# Microcontroller.net
KiCad netlist of a schematic drawn in Altium Designer
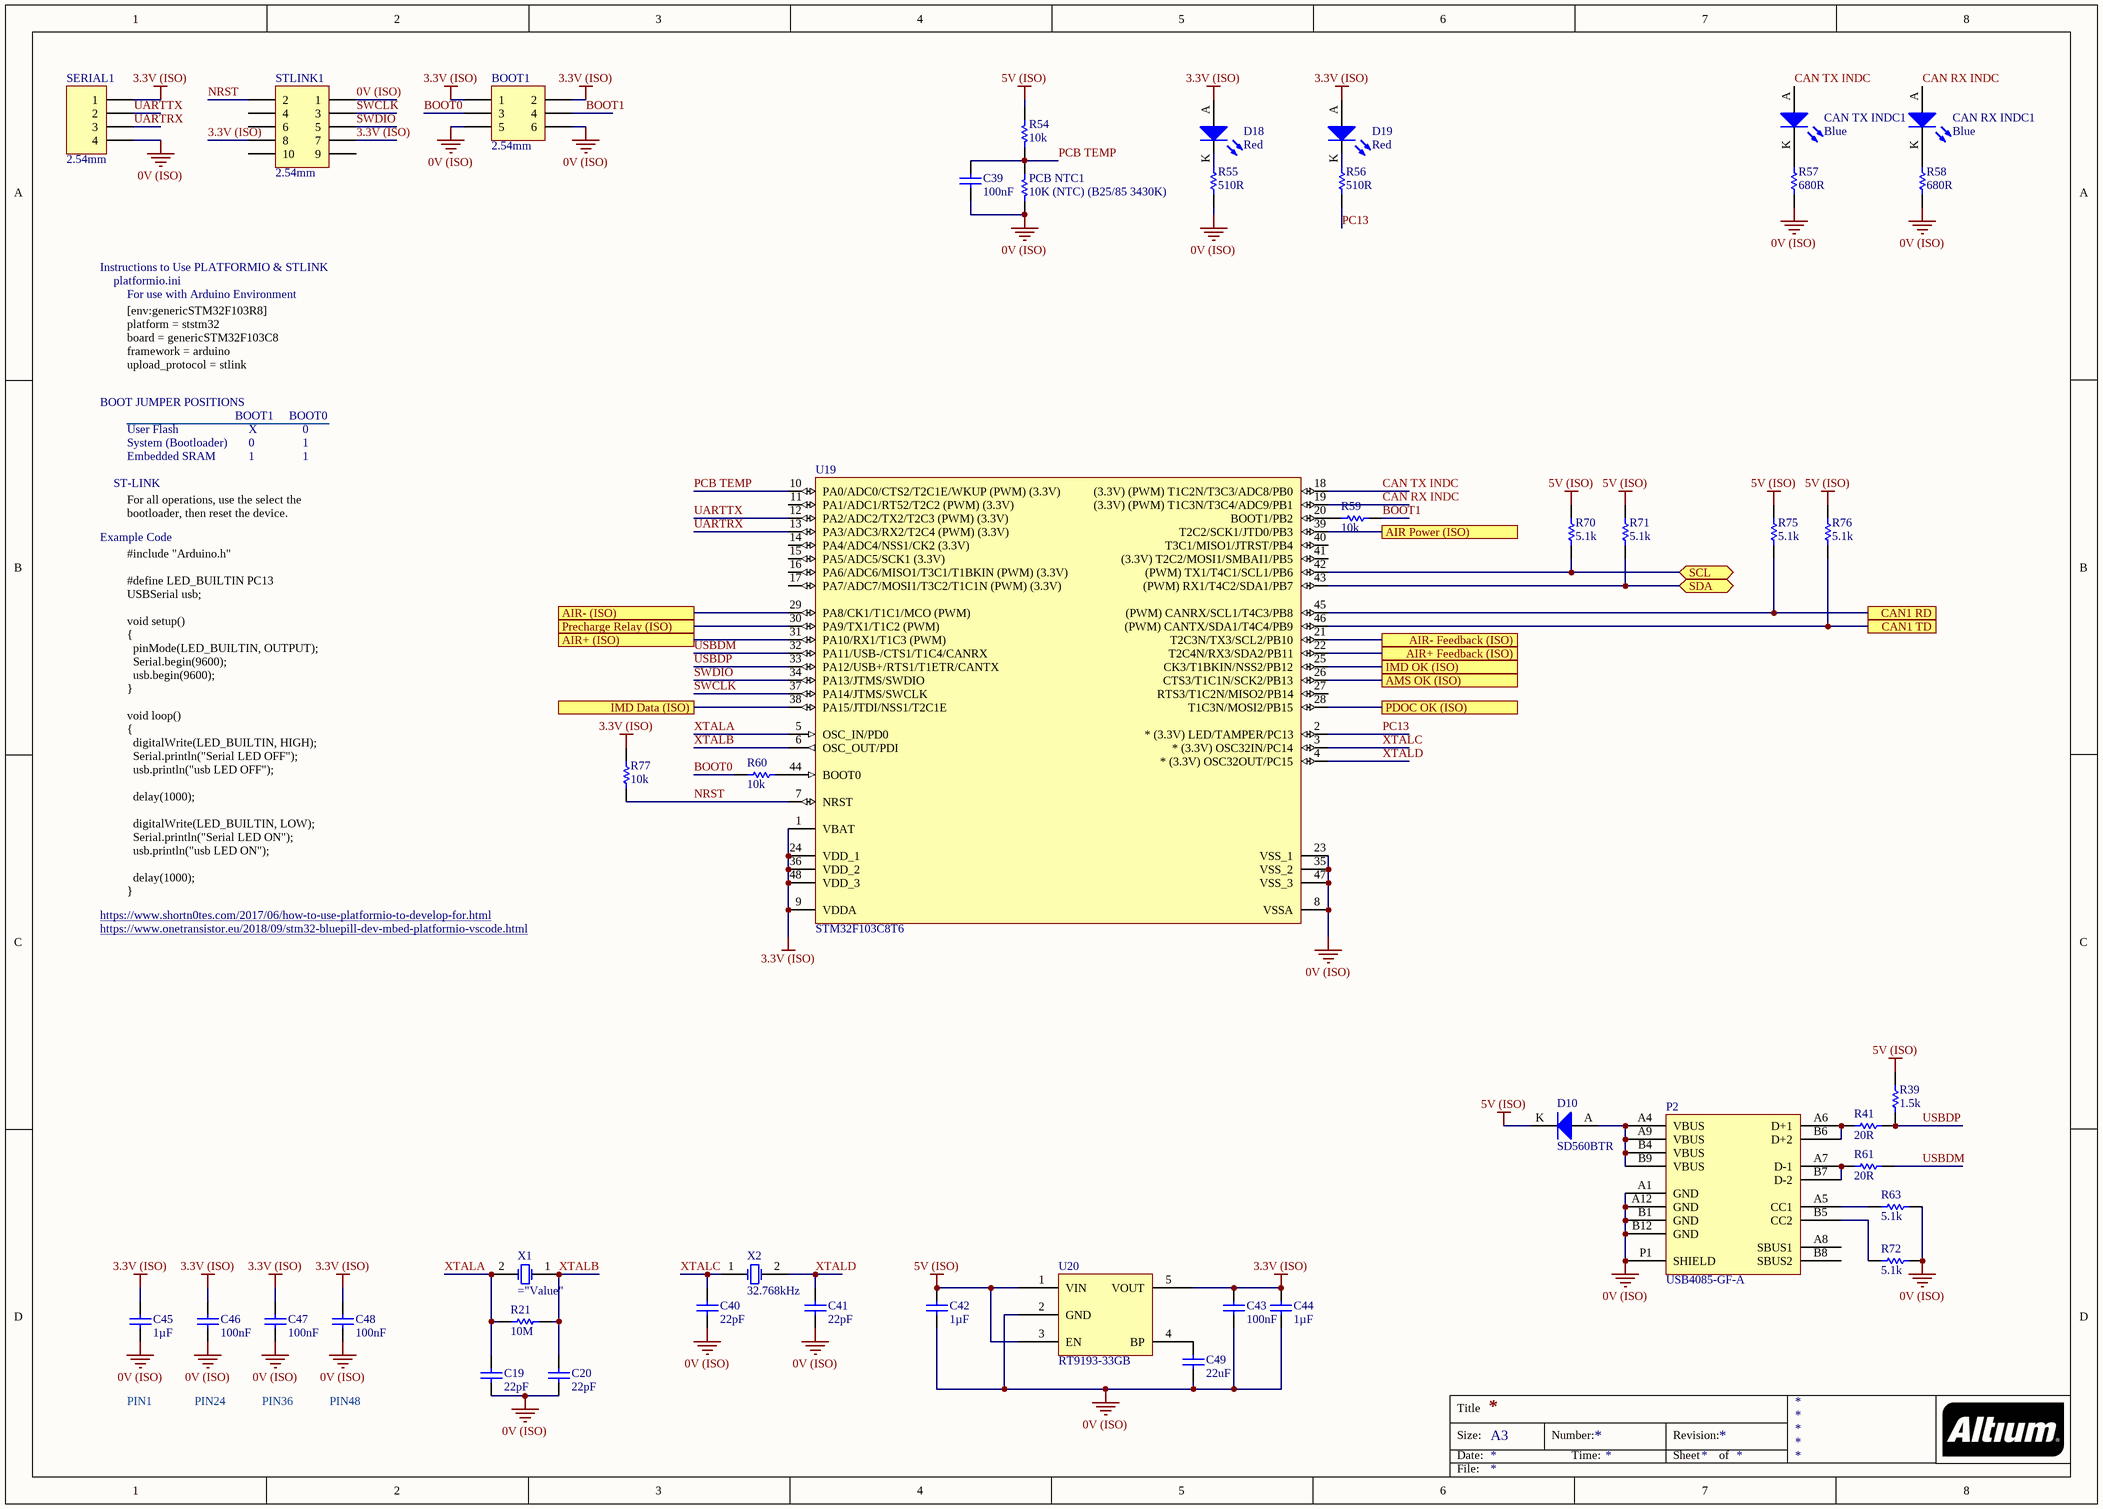
[diagram p0: Microcontroller.SchDoc]

(export (version "E")
  (design (tool "Eeschema 10.0.6"))
  (components
    (comp (ref "BOOT1")
      (value "2.54mm")
      (footprint "TH 2.54mm Header 2x3")
      (fields (field (name "PART NUMBER") "TH 2.54mm Header 2x3") (field (name "CONTACT") "NA"))
      (libsource (lib "ts_20-standard-connectors") (part "Header 2x3"))
    )
    (comp (ref "C19")
      (value "22pF")
      (footprint "0805")
      (fields
        (field (name "PART NUMBER") "GRM21A5C2E220JW01D")
        (field (name "TOLERANCE") "±5%")
        (field (name "MANUFACTURER") "muRata")
      )
      (libsource (lib "ts_20-standard-library") (part "Capacitor"))
    )
    (comp (ref "C20")
      (value "22pF")
      (footprint "0805")
      (fields
        (field (name "PART NUMBER") "GRM21A5C2E220JW01D")
        (field (name "TOLERANCE") "±5%")
        (field (name "MANUFACTURER") "muRata")
      )
      (libsource (lib "ts_20-standard-library") (part "Capacitor"))
    )
    (comp (ref "C39")
      (value "100nF")
      (footprint "0805")
      (fields
        (field (name "PART NUMBER") "GCM21BR71E104KA37L")
        (field (name "TOLERANCE") "10%")
        (field (name "MANUFACTURER") "muRata")
      )
      (libsource (lib "ts_20-standard-library") (part "Capacitor"))
    )
    (comp (ref "C40")
      (value "22pF")
      (footprint "0805")
      (fields
        (field (name "PART NUMBER") "GRM21A5C2E220JW01D")
        (field (name "TOLERANCE") "±5%")
        (field (name "MANUFACTURER") "muRata")
      )
      (libsource (lib "ts_20-standard-library") (part "Capacitor"))
    )
    (comp (ref "C41")
      (value "22pF")
      (footprint "0805")
      (fields
        (field (name "PART NUMBER") "GRM21A5C2E220JW01D")
        (field (name "TOLERANCE") "±5%")
        (field (name "MANUFACTURER") "muRata")
      )
      (libsource (lib "ts_20-standard-library") (part "Capacitor"))
    )
    (comp (ref "C42")
      (value "1µF")
      (footprint "0805")
      (fields
        (field (name "PART NUMBER") "GCM21BR71H105KA03L")
        (field (name "TOLERANCE") "±10%")
        (field (name "MANUFACTURER") "muRata")
      )
      (libsource (lib "ts_20-standard-library") (part "Capacitor"))
    )
    (comp (ref "C43")
      (value "100nF")
      (footprint "0805")
      (fields
        (field (name "PART NUMBER") "GCM21BR71H104KA37L")
        (field (name "TOLERANCE") "±10%")
        (field (name "MANUFACTURER") "muRata")
      )
      (libsource (lib "ts_20-standard-library") (part "Capacitor"))
    )
    (comp (ref "C44")
      (value "1µF")
      (footprint "0805")
      (fields
        (field (name "PART NUMBER") "GCM21BR71H105KA03L")
        (field (name "TOLERANCE") "±10%")
        (field (name "MANUFACTURER") "muRata")
      )
      (libsource (lib "ts_20-standard-library") (part "Capacitor"))
    )
    (comp (ref "C45")
      (value "1µF")
      (footprint "0805")
      (fields
        (field (name "PART NUMBER") "GCM21BR71H105KA03L")
        (field (name "TOLERANCE") "±10%")
        (field (name "MANUFACTURER") "muRata")
      )
      (libsource (lib "ts_20-standard-library") (part "Capacitor"))
    )
    (comp (ref "C46")
      (value "100nF")
      (footprint "0805")
      (fields
        (field (name "PART NUMBER") "GCM21BR71H104KA37L")
        (field (name "TOLERANCE") "±10%")
        (field (name "MANUFACTURER") "muRata")
      )
      (libsource (lib "ts_20-standard-library") (part "Capacitor"))
    )
    (comp (ref "C47")
      (value "100nF")
      (footprint "0805")
      (fields
        (field (name "PART NUMBER") "GCM21BR71H104KA37L")
        (field (name "TOLERANCE") "±10%")
        (field (name "MANUFACTURER") "muRata")
      )
      (libsource (lib "ts_20-standard-library") (part "Capacitor"))
    )
    (comp (ref "C48")
      (value "100nF")
      (footprint "0805")
      (fields
        (field (name "PART NUMBER") "GCM21BR71H104KA37L")
        (field (name "TOLERANCE") "±10%")
        (field (name "MANUFACTURER") "muRata")
      )
      (libsource (lib "ts_20-standard-library") (part "Capacitor"))
    )
    (comp (ref "C49")
      (value "22uF")
      (footprint "0805")
      (fields
        (field (name "PART NUMBER") "GRM21BR61A226ME51L")
        (field (name "TOLERANCE") "20%")
        (field (name "MANUFACTURER") "muRata")
      )
      (libsource (lib "ts_20-standard-library") (part "Capacitor"))
    )
    (comp (ref "CAN RX INDC1")
      (value "Blue")
      (footprint "0805 LED")
      (description "LED BLUE CLEAR 2012 SMD")
      (fields
        (field (name "PART NUMBER") "SML-MN2BCTT86C")
        (field (name "MANUFACTURER") "ROHM Semiconductor")
      )
      (libsource (lib "ts_20-standard-library") (part "LED"))
    )
    (comp (ref "CAN TX INDC1")
      (value "Blue")
      (footprint "0805 LED")
      (description "LED BLUE CLEAR 2012 SMD")
      (fields
        (field (name "PART NUMBER") "SML-MN2BCTT86C")
        (field (name "MANUFACTURER") "ROHM Semiconductor")
      )
      (libsource (lib "ts_20-standard-library") (part "LED"))
    )
    (comp (ref "D10")
      (value "SD560BTR")
      (footprint "SMB Diode")
      (description "1.2V_F 600V 5A SMB")
      (fields
        (field (name "MANUFACTURER") "SMC Diode Solutions")
        (field (name "DIGIKEY PART NUMBER") "1655-1530-2-ND")
      )
      (libsource (lib "ts_20-standard-library") (part "Diode"))
    )
    (comp (ref "D18")
      (value "Red")
      (footprint "0805 LED")
      (description "Red LED Indication - Discrete 1.75V 0805 (2012 Metric)")
      (fields (field (name "MANUFACTURER") "ROHM Semiconductor") (field (name "PART NUMBER") "SML-210LTT86"))
      (libsource (lib "ts_20-standard-library") (part "LED"))
    )
    (comp (ref "D19")
      (value "Red")
      (footprint "0805 LED")
      (description "Red LED Indication - Discrete 1.75V 0805 (2012 Metric)")
      (fields (field (name "MANUFACTURER") "ROHM Semiconductor") (field (name "PART NUMBER") "SML-210LTT86"))
      (libsource (lib "ts_20-standard-library") (part "LED"))
    )
    (comp (ref "P2")
      (value "USB4085-GF-A")
      (footprint "USB4085-GF-A")
      (description "USB - C (Type - C) USB 2.0 Receptacle Connector 16 Position Through Hole, Right Angle")
      (fields (field (name "DIGIKEY PART NUMBER") "2073-USB4085-GF-ACT-ND"))
      (libsource (lib "ts_20-standard-connectors") (part "USB4085-GF-A"))
    )
    (comp (ref "PCB NTC1")
      (value "10K (NTC) (B25/85 3430K)")
      (footprint "0805")
      (fields
        (field (name "PART NUMBER") "NTCS0805E3103FLT")
        (field (name "MANUFACTURER") "Vishay Beyschlag")
        (field (name "TOLERANCE") "0.01")
      )
      (libsource (lib "ts_20-standard-library") (part "Resistor"))
    )
    (comp (ref "R21")
      (value "10M")
      (footprint "0805")
      (fields
        (field (name "PART NUMBER") "RC0805FR0710ML")
        (field (name "MANUFACTURER") "YAGEO")
        (field (name "TOLERANCE") "0.01")
      )
      (libsource (lib "ts_20-standard-library") (part "Resistor"))
    )
    (comp (ref "R39")
      (value "1.5k")
      (footprint "0805")
      (fields
        (field (name "PART NUMBER") "RC0805FR071K5L")
        (field (name "MANUFACTURER") "YAGEO")
        (field (name "TOLERANCE") "0.01")
      )
      (libsource (lib "ts_20-standard-library") (part "Resistor"))
    )
    (comp (ref "R41")
      (value "20R")
      (footprint "0805")
      (fields
        (field (name "PART NUMBER") "RC0805FR0720RL")
        (field (name "MANUFACTURER") "YAGEO")
        (field (name "TOLERANCE") "0.01")
      )
      (libsource (lib "ts_20-standard-library") (part "Resistor"))
    )
    (comp (ref "R54")
      (value "10k")
      (footprint "0805")
      (fields
        (field (name "PART NUMBER") "RC0805FR0710KL")
        (field (name "MANUFACTURER") "YAGEO")
        (field (name "TOLERANCE") "0.01")
      )
      (libsource (lib "ts_20-standard-library") (part "Resistor"))
    )
    (comp (ref "R55")
      (value "510R")
      (footprint "0805")
      (fields
        (field (name "MANUFACTURER") "YAGEO")
        (field (name "PART NUMBER") "RC0805FR07510RL")
        (field (name "TOLERANCE") "0.01")
      )
      (libsource (lib "ts_20-standard-library") (part "Resistor"))
    )
    (comp (ref "R56")
      (value "510R")
      (footprint "0805")
      (fields
        (field (name "MANUFACTURER") "YAGEO")
        (field (name "PART NUMBER") "RC0805FR07510RL")
        (field (name "TOLERANCE") "0.01")
      )
      (libsource (lib "ts_20-standard-library") (part "Resistor"))
    )
    (comp (ref "R57")
      (value "680R")
      (footprint "0805")
      (fields
        (field (name "PART NUMBER") "RC0805FR07680RL")
        (field (name "MANUFACTURER") "YAGEO")
        (field (name "TOLERANCE") "0.01")
      )
      (libsource (lib "ts_20-standard-library") (part "Resistor"))
    )
    (comp (ref "R58")
      (value "680R")
      (footprint "0805")
      (fields
        (field (name "PART NUMBER") "RC0805FR07680RL")
        (field (name "MANUFACTURER") "YAGEO")
        (field (name "TOLERANCE") "0.01")
      )
      (libsource (lib "ts_20-standard-library") (part "Resistor"))
    )
    (comp (ref "R59")
      (value "10k")
      (footprint "0805")
      (fields
        (field (name "PART NUMBER") "RC0805FR0710KL")
        (field (name "MANUFACTURER") "YAGEO")
        (field (name "TOLERANCE") "0.01")
      )
      (libsource (lib "ts_20-standard-library") (part "Resistor"))
    )
    (comp (ref "R60")
      (value "10k")
      (footprint "0805")
      (fields
        (field (name "PART NUMBER") "RC0805FR0710KL")
        (field (name "MANUFACTURER") "YAGEO")
        (field (name "TOLERANCE") "0.01")
      )
      (libsource (lib "ts_20-standard-library") (part "Resistor"))
    )
    (comp (ref "R61")
      (value "20R")
      (footprint "0805")
      (fields
        (field (name "PART NUMBER") "RC0805FR0720RL")
        (field (name "MANUFACTURER") "YAGEO")
        (field (name "TOLERANCE") "0.01")
      )
      (libsource (lib "ts_20-standard-library") (part "Resistor"))
    )
    (comp (ref "R63")
      (value "5.1k")
      (footprint "0805")
      (fields
        (field (name "PART NUMBER") "RC0805FR075K1L")
        (field (name "MANUFACTURER") "YAGEO")
        (field (name "TOLERANCE") "0.01")
      )
      (libsource (lib "ts_20-standard-library") (part "Resistor"))
    )
    (comp (ref "R70")
      (value "5.1k")
      (footprint "0805")
      (fields
        (field (name "PART NUMBER") "RC0805FR075K1L")
        (field (name "MANUFACTURER") "YAGEO")
        (field (name "TOLERANCE") "0.01")
      )
      (libsource (lib "ts_20-standard-library") (part "Resistor"))
    )
    (comp (ref "R71")
      (value "5.1k")
      (footprint "0805")
      (fields
        (field (name "PART NUMBER") "RC0805FR075K1L")
        (field (name "MANUFACTURER") "YAGEO")
        (field (name "TOLERANCE") "0.01")
      )
      (libsource (lib "ts_20-standard-library") (part "Resistor"))
    )
    (comp (ref "R72")
      (value "5.1k")
      (footprint "0805")
      (fields
        (field (name "PART NUMBER") "RC0805FR075K1L")
        (field (name "MANUFACTURER") "YAGEO")
        (field (name "TOLERANCE") "0.01")
      )
      (libsource (lib "ts_20-standard-library") (part "Resistor"))
    )
    (comp (ref "R75")
      (value "5.1k")
      (footprint "0805")
      (fields
        (field (name "PART NUMBER") "RC0805FR075K1L")
        (field (name "MANUFACTURER") "YAGEO")
        (field (name "TOLERANCE") "0.01")
      )
      (libsource (lib "ts_20-standard-library") (part "Resistor"))
    )
    (comp (ref "R76")
      (value "5.1k")
      (footprint "0805")
      (fields
        (field (name "PART NUMBER") "RC0805FR075K1L")
        (field (name "MANUFACTURER") "YAGEO")
        (field (name "TOLERANCE") "0.01")
      )
      (libsource (lib "ts_20-standard-library") (part "Resistor"))
    )
    (comp (ref "R77")
      (value "10k")
      (footprint "0805")
      (fields
        (field (name "MANUFACTURER") "YAGEO")
        (field (name "PART NUMBER") "RC0805FR0710KL")
        (field (name "TOLERANCE") "0.01")
      )
      (libsource (lib "ts_20-standard-library") (part "Resistor"))
    )
    (comp (ref "SERIAL1")
      (value "2.54mm")
      (footprint "TH 2.54mm Header 1x4")
      (fields (field (name "PART NUMBER") "TH 2.54mm Header 1x4") (field (name "CONTACT") "NA"))
      (libsource (lib "ts_20-standard-connectors") (part "Header 1x4"))
    )
    (comp (ref "STLINK1")
      (value "2.54mm")
      (footprint "TH 2.54mm Header 2x5")
      (fields (field (name "PART NUMBER") "TH 2.54mm Header 2x5") (field (name "CONTACT") "NA"))
      (libsource (lib "ts_20-standard-connectors") (part "Header 2x5"))
    )
    (comp (ref "U19")
      (value "STM32F103C8T6")
      (footprint "STM 48-LQFP")
      (description "ARM® Cortex®-M3 STM32F1 Microcontroller IC 32-Bit 72MHz 64KB (64K x 8) FLASH")
      (fields
        (field (name "MANUFACTURER") "STMicroelectronics")
        (field (name "DIGIKEY PART NUMBER") "497-6063-ND")
      )
      (libsource (lib "ts_20-standard-library") (part "STM32F103C8T6"))
    )
    (comp (ref "U20")
      (value "RT9193-33GB")
      (footprint "RICHTEK SOT-23-5")
      (description "IC REG LINEAR 3.3V 300MA SOT23-5")
      (fields (field (name "MANUFACTURER") "Richtek") (field (name "DIGIKEY PART NUMBER") "1028-1014-1-ND"))
      (libsource (lib "ts_20-standard-library") (part "RT9193-33GB"))
    )
    (comp (ref "X1")
      (value "~")
      (footprint "Abracon HC-49/US")
      (fields
        (field (name "PART NUMBER") "ABLS-16.000MHZ-B4-T")
        (field (name "MANUFACTURER") "Abracon LLC")
        (field (name "DIGIKEY PART NUMBER") "535-10226-1-ND")
      )
      (libsource (lib "ts_20-standard-library") (part "Crystal"))
    )
    (comp (ref "X2")
      (value "32.768kHz")
      (footprint "EPSON 2-SMD")
      (fields
        (field (name "PART NUMBER") "FC-135 32.7680KA-A5")
        (field (name "MANUFACTURER") "EPSON")
        (field (name "DIGIKEY PART NUMBER") "SER4103TR-ND")
      )
      (libsource (lib "ts_20-standard-library") (part "Crystal"))
    )
  )
  (nets
    (net (code "1") (name "/AIR Power (ISO)") (class "Default")
      (node (ref "U19") (pin "39") (pinfunction "T2C2/SCK1/JTD0/PB3_39") (pintype "bidirectional"))
    )
    (net (code "2") (name "/AIR+ (ISO)") (class "Default")
      (node (ref "U19") (pin "31") (pinfunction "PA10/RX1/T1C3_(PWM)_31") (pintype "bidirectional"))
    )
    (net (code "3") (name "/AIR+ Feedback (ISO)") (class "Default")
      (node (ref "U19") (pin "22") (pinfunction "T2C4N/RX3/SDA2/PB11_22") (pintype "bidirectional"))
    )
    (net (code "4") (name "/AIR- (ISO)") (class "Default")
      (node (ref "U19") (pin "29") (pinfunction "PA8/CK1/T1C1/MCO_(PWM)_29") (pintype "bidirectional"))
    )
    (net (code "5") (name "/AIR- Feedback (ISO)") (class "Default")
      (node (ref "U19") (pin "21") (pinfunction "T2C3N/TX3/SCL2/PB10_21") (pintype "bidirectional"))
    )
    (net (code "6") (name "/AMS OK (ISO)") (class "Default")
      (node (ref "U19") (pin "26") (pinfunction "CTS3/T1C1N/SCK2/PB13_26") (pintype "bidirectional"))
    )
    (net (code "7") (name "/BOOT0") (class "Default")
      (node (ref "BOOT1") (pin "3") (pinfunction "3_3") (pintype "passive"))
      (node (ref "R60") (pin "1") (pinfunction "1_1") (pintype "passive"))
    )
    (net (code "8") (name "/BOOT1") (class "Default")
      (node (ref "BOOT1") (pin "4") (pinfunction "4_4") (pintype "passive"))
      (node (ref "R59") (pin "2") (pinfunction "2_2") (pintype "passive"))
    )
    (net (code "9") (name "/CAN RX INDC") (class "Default")
      (node (ref "CAN RX INDC1") (pin "A") (pinfunction "A_A") (pintype "passive"))
      (node (ref "U19") (pin "19") (pinfunction "(3.3V)_(PWM)_T1C3N/T3C4/ADC9/PB1_19") (pintype "bidirectional"))
    )
    (net (code "10") (name "/CAN TX INDC") (class "Default")
      (node (ref "CAN TX INDC1") (pin "A") (pinfunction "A_A") (pintype "passive"))
      (node (ref "U19") (pin "18") (pinfunction "(3.3V)_(PWM)_T1C2N/T3C3/ADC8/PB0_18") (pintype "bidirectional"))
    )
    (net (code "11") (name "/CAN1 RD") (class "Default")
      (node (ref "R75") (pin "1") (pinfunction "1_1") (pintype "passive"))
      (node (ref "U19") (pin "45") (pinfunction "(PWM)_CANRX/SCL1/T4C3/PB8_45") (pintype "bidirectional"))
    )
    (net (code "12") (name "/CAN1 TD") (class "Default")
      (node (ref "R76") (pin "1") (pinfunction "1_1") (pintype "passive"))
      (node (ref "U19") (pin "46") (pinfunction "(PWM)_CANTX/SDA1/T4C4/PB9_46") (pintype "bidirectional"))
    )
    (net (code "13") (name "/IMD Data (ISO)") (class "Default")
      (node (ref "U19") (pin "38") (pinfunction "PA15/JTDI/NSS1/T2C1E_38") (pintype "bidirectional"))
    )
    (net (code "14") (name "/IMD OK (ISO)") (class "Default")
      (node (ref "U19") (pin "25") (pinfunction "CK3/T1BKIN/NSS2/PB12_25") (pintype "bidirectional"))
    )
    (net (code "15") (name "/NRST") (class "Default")
      (node (ref "R77") (pin "1") (pinfunction "1_1") (pintype "passive"))
      (node (ref "STLINK1") (pin "2") (pinfunction "2_2") (pintype "passive"))
      (node (ref "U19") (pin "7") (pinfunction "NRST_7") (pintype "bidirectional"))
    )
    (net (code "16") (name "/PC13") (class "Default")
      (node (ref "R56") (pin "1") (pinfunction "1_1") (pintype "passive"))
      (node (ref "U19") (pin "2") (pinfunction "*_(3.3V)_LED/TAMPER/PC13_2") (pintype "bidirectional"))
    )
    (net (code "17") (name "/PCB TEMP") (class "Default")
      (node (ref "C39") (pin "2") (pinfunction "2_2") (pintype "passive"))
      (node (ref "PCB NTC1") (pin "2") (pinfunction "2_2") (pintype "passive"))
      (node (ref "R54") (pin "1") (pinfunction "1_1") (pintype "passive"))
      (node (ref "U19") (pin "10") (pinfunction "PA0/ADC0/CTS2/T2C1E/WKUP_(PWM)_(3.3V)_10") (pintype "bidirectional"))
    )
    (net (code "18") (name "/PDOC OK (ISO)") (class "Default")
      (node (ref "U19") (pin "28") (pinfunction "T1C3N/MOSI2/PB15_28") (pintype "bidirectional"))
    )
    (net (code "19") (name "/Precharge Relay (ISO)") (class "Default")
      (node (ref "U19") (pin "30") (pinfunction "PA9/TX1/T1C2_(PWM)_30") (pintype "bidirectional"))
    )
    (net (code "20") (name "/SCL") (class "Default")
      (node (ref "R70") (pin "1") (pinfunction "1_1") (pintype "passive"))
      (node (ref "U19") (pin "42") (pinfunction "(PWM)_TX1/T4C1/SCL1/PB6_42") (pintype "bidirectional"))
    )
    (net (code "21") (name "/SDA") (class "Default")
      (node (ref "R71") (pin "1") (pinfunction "1_1") (pintype "passive"))
      (node (ref "U19") (pin "43") (pinfunction "(PWM)_RX1/T4C2/SDA1/PB7_43") (pintype "bidirectional"))
    )
    (net (code "22") (name "/SWCLK") (class "Default")
      (node (ref "STLINK1") (pin "3") (pinfunction "3_3") (pintype "passive"))
      (node (ref "U19") (pin "37") (pinfunction "PA14/JTMS/SWCLK_37") (pintype "bidirectional"))
    )
    (net (code "23") (name "/SWDIO") (class "Default")
      (node (ref "STLINK1") (pin "5") (pinfunction "5_5") (pintype "passive"))
      (node (ref "U19") (pin "34") (pinfunction "PA13/JTMS/SWDIO_34") (pintype "bidirectional"))
    )
    (net (code "24") (name "/UARTRX") (class "Default")
      (node (ref "SERIAL1") (pin "3") (pinfunction "3_3") (pintype "passive"))
      (node (ref "U19") (pin "13") (pinfunction "PA3/ADC3/RX2/T2C4_(PWM)_(3.3V)_13") (pintype "bidirectional"))
    )
    (net (code "25") (name "/UARTTX") (class "Default")
      (node (ref "SERIAL1") (pin "2") (pinfunction "2_2") (pintype "passive"))
      (node (ref "U19") (pin "12") (pinfunction "PA2/ADC2/TX2/T2C3_(PWM)_(3.3V)_12") (pintype "bidirectional"))
    )
    (net (code "26") (name "/USBDM") (class "Default")
      (node (ref "R61") (pin "2") (pinfunction "2_2") (pintype "passive"))
      (node (ref "U19") (pin "32") (pinfunction "PA11/USB-/CTS1/T1C4/CANRX_32") (pintype "bidirectional"))
    )
    (net (code "27") (name "/USBDP") (class "Default")
      (node (ref "R39") (pin "1") (pinfunction "1_1") (pintype "passive"))
      (node (ref "R41") (pin "2") (pinfunction "2_2") (pintype "passive"))
      (node (ref "U19") (pin "33") (pinfunction "PA12/USB+/RTS1/T1ETR/CANTX_33") (pintype "bidirectional"))
    )
    (net (code "28") (name "/XTALA") (class "Default")
      (node (ref "C19") (pin "2") (pinfunction "2_2") (pintype "passive"))
      (node (ref "R21") (pin "2") (pinfunction "2_2") (pintype "passive"))
      (node (ref "U19") (pin "5") (pinfunction "OSC_IN/PD0_5") (pintype "input"))
      (node (ref "X1") (pin "2") (pinfunction "OSC2_2") (pintype "passive"))
    )
    (net (code "29") (name "/XTALB") (class "Default")
      (node (ref "C20") (pin "2") (pinfunction "2_2") (pintype "passive"))
      (node (ref "R21") (pin "1") (pinfunction "1_1") (pintype "passive"))
      (node (ref "U19") (pin "6") (pinfunction "OSC_OUT/PDI_6") (pintype "output"))
      (node (ref "X1") (pin "1") (pinfunction "OSC1_1") (pintype "passive"))
    )
    (net (code "30") (name "/XTALC") (class "Default")
      (node (ref "C40") (pin "2") (pinfunction "2_2") (pintype "passive"))
      (node (ref "U19") (pin "3") (pinfunction "*_(3.3V)_OSC32IN/PC14_3") (pintype "bidirectional"))
      (node (ref "X2") (pin "1") (pinfunction "OSC1_1") (pintype "passive"))
    )
    (net (code "31") (name "/XTALD") (class "Default")
      (node (ref "C41") (pin "2") (pinfunction "2_2") (pintype "passive"))
      (node (ref "U19") (pin "4") (pinfunction "*_(3.3V)_OSC32OUT/PC15_4") (pintype "bidirectional"))
      (node (ref "X2") (pin "2") (pinfunction "OSC2_2") (pintype "passive"))
    )
    (net (code "32") (name "0V (ISO)") (class "Default")
      (node (ref "BOOT1") (pin "5") (pinfunction "5_5") (pintype "passive"))
      (node (ref "BOOT1") (pin "6") (pinfunction "6_6") (pintype "passive"))
      (node (ref "C19") (pin "1") (pinfunction "1_1") (pintype "passive"))
      (node (ref "C20") (pin "1") (pinfunction "1_1") (pintype "passive"))
      (node (ref "C39") (pin "1") (pinfunction "1_1") (pintype "passive"))
      (node (ref "C40") (pin "1") (pinfunction "1_1") (pintype "passive"))
      (node (ref "C41") (pin "1") (pinfunction "1_1") (pintype "passive"))
      (node (ref "C42") (pin "1") (pinfunction "1_1") (pintype "passive"))
      (node (ref "C43") (pin "1") (pinfunction "1_1") (pintype "passive"))
      (node (ref "C44") (pin "1") (pinfunction "1_1") (pintype "passive"))
      (node (ref "C45") (pin "1") (pinfunction "1_1") (pintype "passive"))
      (node (ref "C46") (pin "1") (pinfunction "1_1") (pintype "passive"))
      (node (ref "C47") (pin "1") (pinfunction "1_1") (pintype "passive"))
      (node (ref "C48") (pin "1") (pinfunction "1_1") (pintype "passive"))
      (node (ref "C49") (pin "1") (pinfunction "1_1") (pintype "passive"))
      (node (ref "P2") (pin "A1") (pinfunction "GND_A1") (pintype "passive"))
      (node (ref "P2") (pin "A12") (pinfunction "GND_A12") (pintype "passive"))
      (node (ref "P2") (pin "B1") (pinfunction "GND_B1") (pintype "passive"))
      (node (ref "P2") (pin "B12") (pinfunction "GND_B12") (pintype "passive"))
      (node (ref "P2") (pin "P1") (pinfunction "SHIELD_P1") (pintype "passive"))
      (node (ref "PCB NTC1") (pin "1") (pinfunction "1_1") (pintype "passive"))
      (node (ref "R55") (pin "1") (pinfunction "1_1") (pintype "passive"))
      (node (ref "R57") (pin "1") (pinfunction "1_1") (pintype "passive"))
      (node (ref "R58") (pin "1") (pinfunction "1_1") (pintype "passive"))
      (node (ref "R63") (pin "2") (pinfunction "2_2") (pintype "passive"))
      (node (ref "R72") (pin "2") (pinfunction "2_2") (pintype "passive"))
      (node (ref "SERIAL1") (pin "4") (pinfunction "4_4") (pintype "passive"))
      (node (ref "STLINK1") (pin "1") (pinfunction "1_1") (pintype "passive"))
      (node (ref "U19") (pin "23") (pinfunction "VSS_1_23") (pintype "power_in"))
      (node (ref "U19") (pin "35") (pinfunction "VSS_2_35") (pintype "power_in"))
      (node (ref "U19") (pin "47") (pinfunction "VSS_3_47") (pintype "power_in"))
      (node (ref "U19") (pin "8") (pinfunction "VSSA_8") (pintype "power_in"))
      (node (ref "U20") (pin "2") (pinfunction "GND_2") (pintype "passive"))
    )
    (net (code "33") (name "3.3V (ISO)") (class "Default")
      (node (ref "BOOT1") (pin "1") (pinfunction "1_1") (pintype "passive"))
      (node (ref "BOOT1") (pin "2") (pinfunction "2_2") (pintype "passive"))
      (node (ref "C43") (pin "2") (pinfunction "2_2") (pintype "passive"))
      (node (ref "C44") (pin "2") (pinfunction "2_2") (pintype "passive"))
      (node (ref "C45") (pin "2") (pinfunction "2_2") (pintype "passive"))
      (node (ref "C46") (pin "2") (pinfunction "2_2") (pintype "passive"))
      (node (ref "C47") (pin "2") (pinfunction "2_2") (pintype "passive"))
      (node (ref "C48") (pin "2") (pinfunction "2_2") (pintype "passive"))
      (node (ref "D18") (pin "A") (pinfunction "A_A") (pintype "passive"))
      (node (ref "D19") (pin "A") (pinfunction "A_A") (pintype "passive"))
      (node (ref "R77") (pin "2") (pinfunction "2_2") (pintype "passive"))
      (node (ref "SERIAL1") (pin "1") (pinfunction "1_1") (pintype "passive"))
      (node (ref "STLINK1") (pin "7") (pinfunction "7_7") (pintype "passive"))
      (node (ref "STLINK1") (pin "8") (pinfunction "8_8") (pintype "passive"))
      (node (ref "U19") (pin "1") (pinfunction "VBAT_1") (pintype "power_in"))
      (node (ref "U19") (pin "24") (pinfunction "VDD_1_24") (pintype "power_in"))
      (node (ref "U19") (pin "36") (pinfunction "VDD_2_36") (pintype "power_in"))
      (node (ref "U19") (pin "48") (pinfunction "VDD_3_48") (pintype "power_in"))
      (node (ref "U19") (pin "9") (pinfunction "VDDA_9") (pintype "power_in"))
      (node (ref "U20") (pin "5") (pinfunction "VOUT_5") (pintype "passive"))
    )
    (net (code "34") (name "5V (ISO)") (class "Default")
      (node (ref "C42") (pin "2") (pinfunction "2_2") (pintype "passive"))
      (node (ref "D10") (pin "K") (pinfunction "K_K") (pintype "passive"))
      (node (ref "R39") (pin "2") (pinfunction "2_2") (pintype "passive"))
      (node (ref "R54") (pin "2") (pinfunction "2_2") (pintype "passive"))
      (node (ref "R70") (pin "2") (pinfunction "2_2") (pintype "passive"))
      (node (ref "R71") (pin "2") (pinfunction "2_2") (pintype "passive"))
      (node (ref "R75") (pin "2") (pinfunction "2_2") (pintype "passive"))
      (node (ref "R76") (pin "2") (pinfunction "2_2") (pintype "passive"))
      (node (ref "U20") (pin "1") (pinfunction "VIN_1") (pintype "passive"))
      (node (ref "U20") (pin "3") (pinfunction "EN_3") (pintype "passive"))
    )
    (net (code "35") (name "Net-(CAN RX INDC1-PadK)") (class "Default")
      (node (ref "CAN RX INDC1") (pin "K") (pinfunction "K_K") (pintype "passive"))
      (node (ref "R58") (pin "2") (pinfunction "2_2") (pintype "passive"))
    )
    (net (code "36") (name "Net-(CAN TX INDC1-PadK)") (class "Default")
      (node (ref "CAN TX INDC1") (pin "K") (pinfunction "K_K") (pintype "passive"))
      (node (ref "R57") (pin "2") (pinfunction "2_2") (pintype "passive"))
    )
    (net (code "37") (name "Net-(D10-PadA)") (class "Default")
      (node (ref "D10") (pin "A") (pinfunction "A_A") (pintype "passive"))
      (node (ref "P2") (pin "A4") (pinfunction "VBUS_A4") (pintype "passive"))
      (node (ref "P2") (pin "A9") (pinfunction "VBUS_A9") (pintype "passive"))
      (node (ref "P2") (pin "B4") (pinfunction "VBUS_B4") (pintype "passive"))
      (node (ref "P2") (pin "B9") (pinfunction "VBUS_B9") (pintype "passive"))
    )
    (net (code "38") (name "Net-(D18-PadK)") (class "Default")
      (node (ref "D18") (pin "K") (pinfunction "K_K") (pintype "passive"))
      (node (ref "R55") (pin "2") (pinfunction "2_2") (pintype "passive"))
    )
    (net (code "39") (name "Net-(D19-PadK)") (class "Default")
      (node (ref "D19") (pin "K") (pinfunction "K_K") (pintype "passive"))
      (node (ref "R56") (pin "2") (pinfunction "2_2") (pintype "passive"))
    )
    (net (code "40") (name "Net-(P2-CC1)") (class "Default")
      (node (ref "P2") (pin "A5") (pinfunction "CC1_A5") (pintype "passive"))
      (node (ref "R63") (pin "1") (pinfunction "1_1") (pintype "passive"))
    )
    (net (code "41") (name "Net-(P2-CC2)") (class "Default")
      (node (ref "P2") (pin "B5") (pinfunction "CC2_B5") (pintype "passive"))
      (node (ref "R72") (pin "1") (pinfunction "1_1") (pintype "passive"))
    )
    (net (code "42") (name "Net-(P2-D+1)") (class "Default")
      (node (ref "P2") (pin "A6") (pinfunction "D+1_A6") (pintype "passive"))
      (node (ref "P2") (pin "B6") (pinfunction "D+2_B6") (pintype "passive"))
      (node (ref "R41") (pin "1") (pinfunction "1_1") (pintype "passive"))
    )
    (net (code "43") (name "Net-(P2-D-1)") (class "Default")
      (node (ref "P2") (pin "A7") (pinfunction "D-1_A7") (pintype "passive"))
      (node (ref "P2") (pin "B7") (pinfunction "D-2_B7") (pintype "passive"))
      (node (ref "R61") (pin "1") (pinfunction "1_1") (pintype "passive"))
    )
    (net (code "44") (name "Net-(U19-BOOT0)") (class "Default")
      (node (ref "R60") (pin "2") (pinfunction "2_2") (pintype "passive"))
      (node (ref "U19") (pin "44") (pinfunction "BOOT0_44") (pintype "input"))
    )
    (net (code "45") (name "Net-(U19-BOOT1{slash}PB2)") (class "Default")
      (node (ref "R59") (pin "1") (pinfunction "1_1") (pintype "passive"))
      (node (ref "U19") (pin "20") (pinfunction "BOOT1/PB2_20") (pintype "bidirectional"))
    )
    (net (code "46") (name "Net-(U20-BP)") (class "Default")
      (node (ref "C49") (pin "2") (pinfunction "2_2") (pintype "passive"))
      (node (ref "U20") (pin "4") (pinfunction "BP_4") (pintype "passive"))
    )
    (net (code "47") (name "unconnected-(P2-SBUS1-PadA8)") (class "Default")
      (node (ref "P2") (pin "A8") (pinfunction "SBUS1_A8") (pintype "passive"))
    )
    (net (code "48") (name "unconnected-(P2-SBUS2-PadB8)") (class "Default")
      (node (ref "P2") (pin "B8") (pinfunction "SBUS2_B8") (pintype "passive"))
    )
    (net (code "49") (name "unconnected-(STLINK1-Pad4)") (class "Default")
      (node (ref "STLINK1") (pin "4") (pinfunction "4_4") (pintype "passive"))
    )
    (net (code "50") (name "unconnected-(STLINK1-Pad6)") (class "Default")
      (node (ref "STLINK1") (pin "6") (pinfunction "6_6") (pintype "passive"))
    )
    (net (code "51") (name "unconnected-(STLINK1-Pad9)") (class "Default")
      (node (ref "STLINK1") (pin "9") (pinfunction "9_9") (pintype "passive"))
    )
    (net (code "52") (name "unconnected-(STLINK1-Pad10)") (class "Default")
      (node (ref "STLINK1") (pin "10") (pinfunction "10_10") (pintype "passive"))
    )
    (net (code "53") (name "unconnected-(U19-(3.3V)_T2C2{slash}MOSI1{slash}SMBAI1{slash}PB5-Pad41)") (class "Default")
      (node (ref "U19") (pin "41") (pinfunction "(3.3V)_T2C2/MOSI1/SMBAI1/PB5_41") (pintype "bidirectional"))
    )
    (net (code "54") (name "unconnected-(U19-PA1{slash}ADC1{slash}RT52{slash}T2C2_(PWM)_(3.3V)-Pad11)") (class "Default")
      (node (ref "U19") (pin "11") (pinfunction "PA1/ADC1/RT52/T2C2_(PWM)_(3.3V)_11") (pintype "bidirectional"))
    )
    (net (code "55") (name "unconnected-(U19-PA4{slash}ADC4{slash}NSS1{slash}CK2_(3.3V)-Pad14)") (class "Default")
      (node (ref "U19") (pin "14") (pinfunction "PA4/ADC4/NSS1/CK2_(3.3V)_14") (pintype "bidirectional"))
    )
    (net (code "56") (name "unconnected-(U19-PA5{slash}ADC5{slash}SCK1_(3.3V)-Pad15)") (class "Default")
      (node (ref "U19") (pin "15") (pinfunction "PA5/ADC5/SCK1_(3.3V)_15") (pintype "bidirectional"))
    )
    (net (code "57") (name "unconnected-(U19-PA6{slash}ADC6{slash}MISO1{slash}T3C1{slash}T1BKIN_(PWM)_(3.3V)-Pad16)") (class "Default")
      (node (ref "U19") (pin "16") (pinfunction "PA6/ADC6/MISO1/T3C1/T1BKIN_(PWM)_(3.3V)_16") (pintype "bidirectional"))
    )
    (net (code "58") (name "unconnected-(U19-PA7{slash}ADC7{slash}MOSI1{slash}T3C2{slash}T1C1N_(PWM)_(3.3V)-Pad17)") (class "Default")
      (node (ref "U19") (pin "17") (pinfunction "PA7/ADC7/MOSI1/T3C2/T1C1N_(PWM)_(3.3V)_17") (pintype "bidirectional"))
    )
    (net (code "59") (name "unconnected-(U19-RTS3{slash}T1C2N{slash}MISO2{slash}PB14-Pad27)") (class "Default")
      (node (ref "U19") (pin "27") (pinfunction "RTS3/T1C2N/MISO2/PB14_27") (pintype "bidirectional"))
    )
    (net (code "60") (name "unconnected-(U19-T3C1{slash}MISO1{slash}JTRST{slash}PB4-Pad40)") (class "Default")
      (node (ref "U19") (pin "40") (pinfunction "T3C1/MISO1/JTRST/PB4_40") (pintype "bidirectional"))
    )
  )
)
